# 1-Schematic_ESP8266.net
KiCad netlist of a schematic drawn in EasyEDA
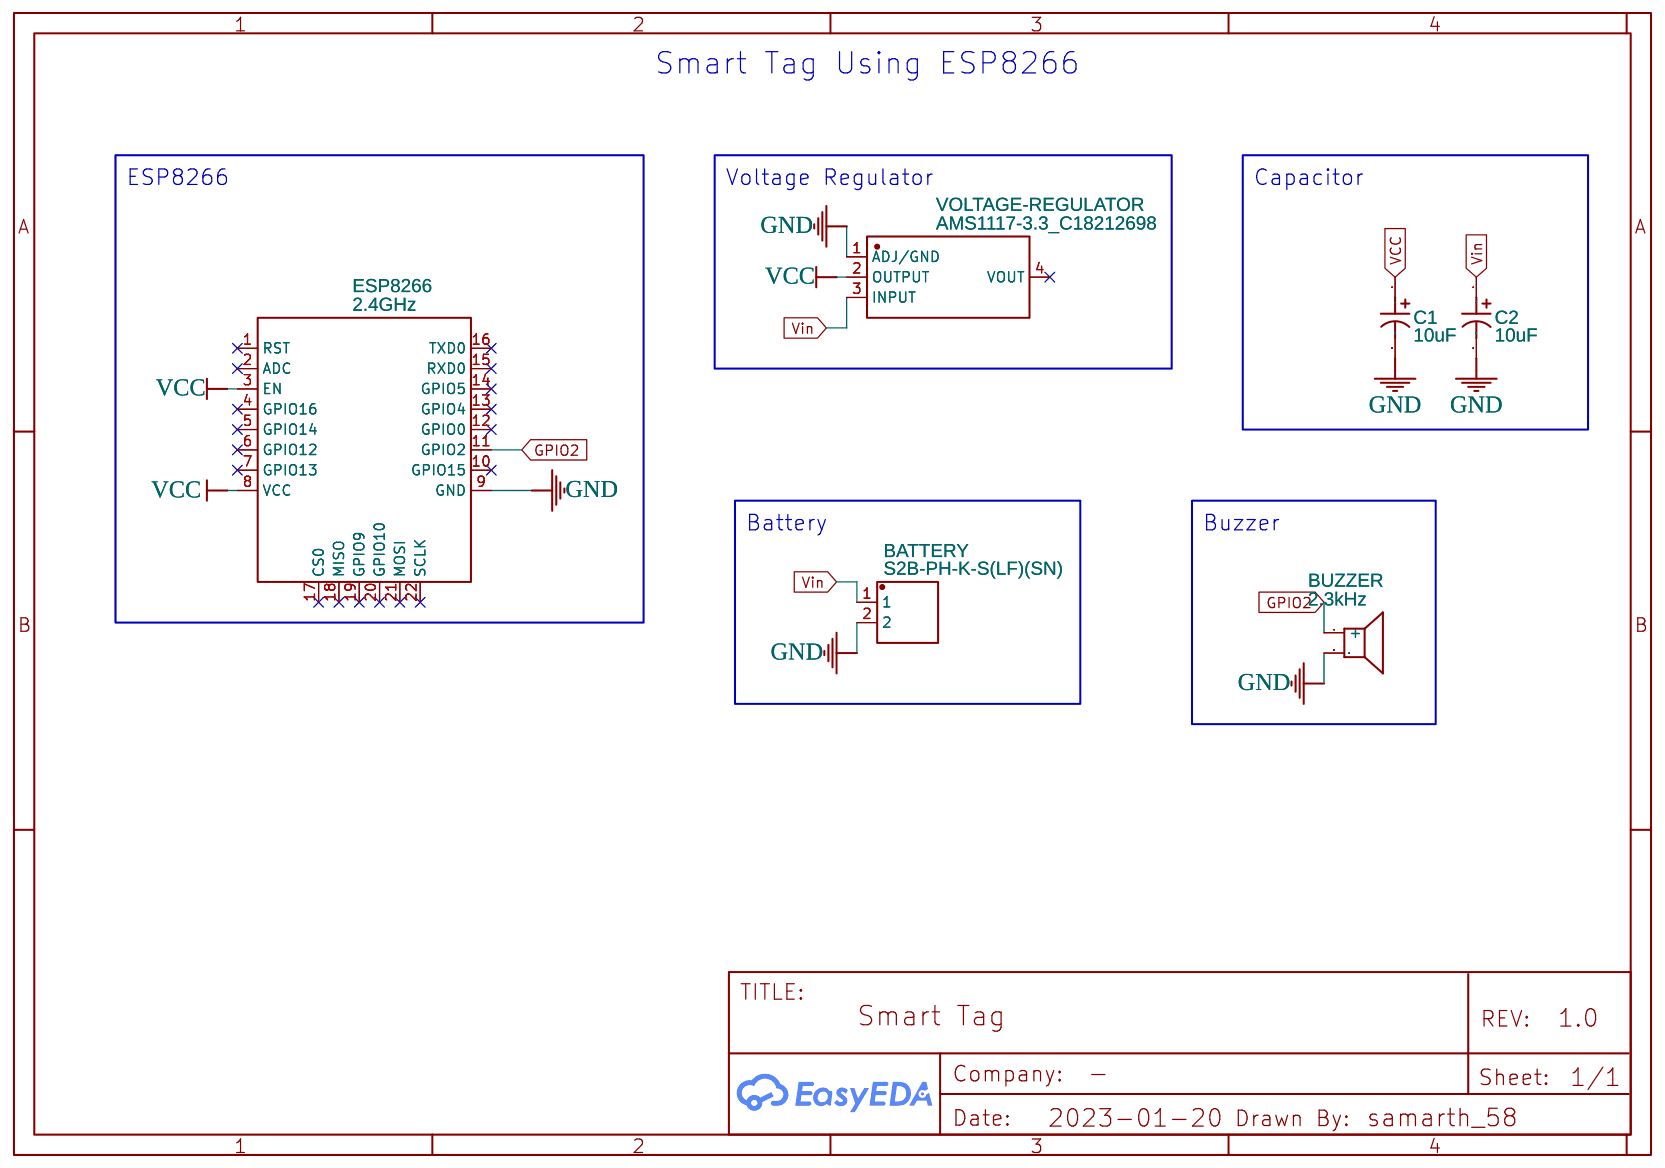
[diagram p0: schematic sheet]

(export (version "E")
  (design (tool "Eeschema 10.0.6"))
  (components
    (comp (ref "BATTERY")
      (value "S2B-PH-K-S(LF)(SN)")
      (fields (field (name "Manufacturer") "JST"))
      (libsource (lib "") (part "S2B-PH-K-S(LF)(SN)"))
    )
    (comp (ref "BUZZER")
      (value "2.3kHz")
      (fields (field (name "Manufacturer Part") "TMB12A05") (field (name "Manufacturer") "华能"))
      (libsource (lib "") (part "TMB12A05"))
    )
    (comp (ref "C1")
      (value "10uF")
      (fields (field (name "Manufacturer Part") "RST10UF16V013") (field (name "Manufacturer") "KNSCHA(科尼盛)"))
      (libsource (lib "") (part "RST10UF16V013"))
    )
    (comp (ref "C2")
      (value "10uF")
      (fields (field (name "Manufacturer Part") "RST10UF16V013") (field (name "Manufacturer") "KNSCHA(科尼盛)"))
      (libsource (lib "") (part "RST10UF16V013"))
    )
    (comp (ref "ESP8266")
      (value "2.4GHz")
      (fields
        (field (name "Manufacturer Part") "ESP-12F(ESP8266MOD)")
        (field (name "Manufacturer") "Ai-Thinker(安信可)")
      )
      (libsource (lib "") (part "ESP-12F(ESP8266MOD)"))
    )
    (comp (ref "VOLTAGE-REGULATOR")
      (value "AMS1117-3.3_C18212698")
      (fields
        (field (name "Manufacturer Part") "AMS1117-3.3")
        (field (name "Manufacturer") "TECH PUBLIC(台舟)")
      )
      (libsource (lib "") (part "AMS1117-3.3_C18212698"))
    )
  )
  (nets
    (net (code "1") (name "GND") (class "Default")
      (node (ref "BATTERY") (pin "2") (pinfunction "2_2") (pintype "unspecified"))
      (node (ref "BUZZER") (pin "2") (pinfunction "2_2") (pintype "unspecified"))
      (node (ref "C1") (pin "2") (pinfunction "2_2") (pintype "input"))
      (node (ref "C2") (pin "2") (pinfunction "2_2") (pintype "input"))
      (node (ref "ESP8266") (pin "9") (pinfunction "GND_9") (pintype "unspecified"))
      (node (ref "VOLTAGE-REGULATOR") (pin "1") (pinfunction "ADJ/GND_1") (pintype "unspecified"))
    )
    (net (code "2") (name "GPIO2") (class "Default")
      (node (ref "BUZZER") (pin "1") (pinfunction "+_1") (pintype "unspecified"))
      (node (ref "ESP8266") (pin "11") (pinfunction "GPIO2_11") (pintype "unspecified"))
    )
    (net (code "3") (name "VCC") (class "Default")
      (node (ref "C1") (pin "1") (pinfunction "1_1") (pintype "input"))
      (node (ref "ESP8266") (pin "3") (pinfunction "EN_3") (pintype "unspecified"))
      (node (ref "ESP8266") (pin "8") (pinfunction "VCC_8") (pintype "unspecified"))
      (node (ref "VOLTAGE-REGULATOR") (pin "2") (pinfunction "OUTPUT_2") (pintype "unspecified"))
    )
    (net (code "4") (name "Vin") (class "Default")
      (node (ref "BATTERY") (pin "1") (pinfunction "1_1") (pintype "unspecified"))
      (node (ref "C2") (pin "1") (pinfunction "1_1") (pintype "input"))
      (node (ref "VOLTAGE-REGULATOR") (pin "3") (pinfunction "INPUT_3") (pintype "unspecified"))
    )
    (net (code "5") (name "unconnected-(ESP8266-ADC-Pad2)") (class "Default")
      (node (ref "ESP8266") (pin "2") (pinfunction "ADC_2") (pintype "unspecified+no_connect"))
    )
    (net (code "6") (name "unconnected-(ESP8266-CS0-Pad17)") (class "Default")
      (node (ref "ESP8266") (pin "17") (pinfunction "CS0_17") (pintype "unspecified+no_connect"))
    )
    (net (code "7") (name "unconnected-(ESP8266-GPIO0-Pad12)") (class "Default")
      (node (ref "ESP8266") (pin "12") (pinfunction "GPIO0_12") (pintype "unspecified+no_connect"))
    )
    (net (code "8") (name "unconnected-(ESP8266-GPIO4-Pad13)") (class "Default")
      (node (ref "ESP8266") (pin "13") (pinfunction "GPIO4_13") (pintype "unspecified+no_connect"))
    )
    (net (code "9") (name "unconnected-(ESP8266-GPIO5-Pad14)") (class "Default")
      (node (ref "ESP8266") (pin "14") (pinfunction "GPIO5_14") (pintype "unspecified+no_connect"))
    )
    (net (code "10") (name "unconnected-(ESP8266-GPIO9-Pad19)") (class "Default")
      (node (ref "ESP8266") (pin "19") (pinfunction "GPIO9_19") (pintype "unspecified+no_connect"))
    )
    (net (code "11") (name "unconnected-(ESP8266-GPIO10-Pad20)") (class "Default")
      (node (ref "ESP8266") (pin "20") (pinfunction "GPIO10_20") (pintype "unspecified+no_connect"))
    )
    (net (code "12") (name "unconnected-(ESP8266-GPIO12-Pad6)") (class "Default")
      (node (ref "ESP8266") (pin "6") (pinfunction "GPIO12_6") (pintype "unspecified+no_connect"))
    )
    (net (code "13") (name "unconnected-(ESP8266-GPIO13-Pad7)") (class "Default")
      (node (ref "ESP8266") (pin "7") (pinfunction "GPIO13_7") (pintype "unspecified+no_connect"))
    )
    (net (code "14") (name "unconnected-(ESP8266-GPIO14-Pad5)") (class "Default")
      (node (ref "ESP8266") (pin "5") (pinfunction "GPIO14_5") (pintype "unspecified+no_connect"))
    )
    (net (code "15") (name "unconnected-(ESP8266-GPIO15-Pad10)") (class "Default")
      (node (ref "ESP8266") (pin "10") (pinfunction "GPIO15_10") (pintype "unspecified+no_connect"))
    )
    (net (code "16") (name "unconnected-(ESP8266-GPIO16-Pad4)") (class "Default")
      (node (ref "ESP8266") (pin "4") (pinfunction "GPIO16_4") (pintype "unspecified+no_connect"))
    )
    (net (code "17") (name "unconnected-(ESP8266-MISO-Pad18)") (class "Default")
      (node (ref "ESP8266") (pin "18") (pinfunction "MISO_18") (pintype "unspecified+no_connect"))
    )
    (net (code "18") (name "unconnected-(ESP8266-MOSI-Pad21)") (class "Default")
      (node (ref "ESP8266") (pin "21") (pinfunction "MOSI_21") (pintype "unspecified+no_connect"))
    )
    (net (code "19") (name "unconnected-(ESP8266-RST-Pad1)") (class "Default")
      (node (ref "ESP8266") (pin "1") (pinfunction "RST_1") (pintype "unspecified+no_connect"))
    )
    (net (code "20") (name "unconnected-(ESP8266-RXD0-Pad15)") (class "Default")
      (node (ref "ESP8266") (pin "15") (pinfunction "RXD0_15") (pintype "unspecified+no_connect"))
    )
    (net (code "21") (name "unconnected-(ESP8266-SCLK-Pad22)") (class "Default")
      (node (ref "ESP8266") (pin "22") (pinfunction "SCLK_22") (pintype "unspecified+no_connect"))
    )
    (net (code "22") (name "unconnected-(ESP8266-TXD0-Pad16)") (class "Default")
      (node (ref "ESP8266") (pin "16") (pinfunction "TXD0_16") (pintype "unspecified+no_connect"))
    )
    (net (code "23") (name "unconnected-(VOLTAGE-REGULATOR-VOUT-Pad4)") (class "Default")
      (node (ref "VOLTAGE-REGULATOR") (pin "4") (pinfunction "VOUT_4") (pintype "unspecified+no_connect"))
    )
  )
)
